# nivel0-2.net
KiCad netlist of a schematic drawn in EAGLE
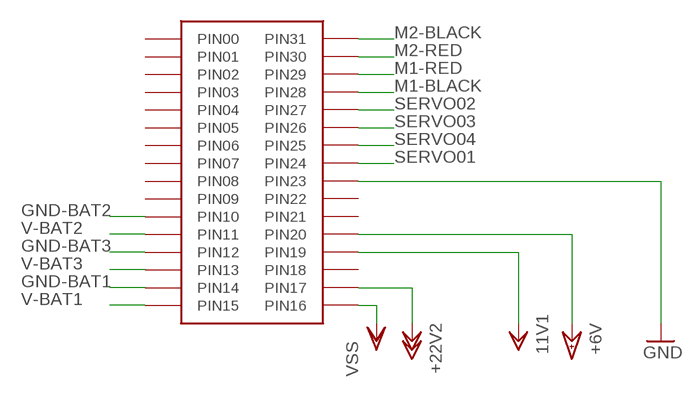
[diagram p0: schematic, sheet 1]
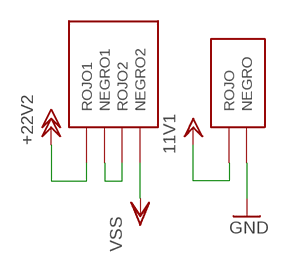
[diagram p1: schematic, sheet 2]
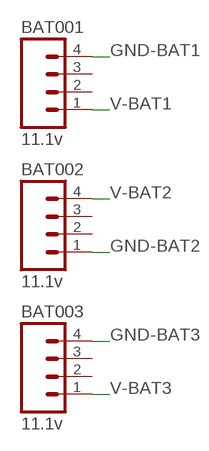
[diagram p2: schematic, sheet 3]
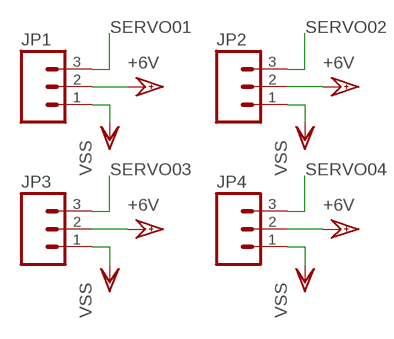
[diagram p3: schematic, sheet 4]
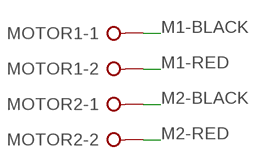
[diagram p4: schematic, sheet 5]

(export (version "E")
  (design (tool "Eeschema 10.0.6"))
  (components
    (comp (ref "U$11")
      (value "CONECTOR_AUDIO")
      (footprint "eagle-import:CONECTOR_AUDIO")
      (libsource (lib "eagle-import") (part "CONECTOR_AUDIO"))
    )
    (comp (ref "U$12")
      (value "CONECTOR_AUDIO2")
      (footprint "eagle-import:CONECTOR_AUDIO2")
      (libsource (lib "eagle-import") (part "CONECTOR_AUDIO2"))
    )
    (comp (ref "BAT001")
      (value "11.1v")
      (footprint "eagle-import:1X04_LONGPADS")
      (libsource (lib "eagle-import") (part "M04LONGPADS"))
    )
    (comp (ref "BAT002")
      (value "11.1v")
      (footprint "eagle-import:1X04_LONGPADS")
      (libsource (lib "eagle-import") (part "M04LONGPADS"))
    )
    (comp (ref "BAT003")
      (value "11.1v")
      (footprint "eagle-import:1X04_LONGPADS")
      (libsource (lib "eagle-import") (part "M04LONGPADS"))
    )
    (comp (ref "MOTOR1")
      (value "W237-02P")
      (footprint "eagle-import:W237-132")
      (libsource (lib "eagle-import") (part "W237-02P"))
    )
    (comp (ref "MOTOR2")
      (value "W237-02P")
      (footprint "eagle-import:W237-132")
      (libsource (lib "eagle-import") (part "W237-02P"))
    )
    (comp (ref "JP1")
      (value "M03LONGPADS")
      (footprint "eagle-import:1X03_LONGPADS")
      (libsource (lib "eagle-import") (part "M03LONGPADS"))
    )
    (comp (ref "JP2")
      (value "M03LONGPADS")
      (footprint "eagle-import:1X03_LONGPADS")
      (libsource (lib "eagle-import") (part "M03LONGPADS"))
    )
    (comp (ref "JP3")
      (value "M03LONGPADS")
      (footprint "eagle-import:1X03_LONGPADS")
      (libsource (lib "eagle-import") (part "M03LONGPADS"))
    )
    (comp (ref "JP4")
      (value "M03LONGPADS")
      (footprint "eagle-import:1X03_LONGPADS")
      (libsource (lib "eagle-import") (part "M03LONGPADS"))
    )
    (comp (ref "U$1")
      (value "BASE")
      (footprint "eagle-import:BASE")
      (libsource (lib "eagle-import") (part "BASE"))
    )
  )
  (nets
    (net (code "1") (name "+6V") (class "Default")
      (node (ref "JP1") (pin "2") (pinfunction "2_2") (pintype "passive"))
      (node (ref "JP2") (pin "2") (pinfunction "2_2") (pintype "passive"))
      (node (ref "JP3") (pin "2") (pinfunction "2_2") (pintype "passive"))
      (node (ref "JP4") (pin "2") (pinfunction "2_2") (pintype "passive"))
      (node (ref "U$1") (pin "PIN20") (pinfunction "PIN20_PIN20") (pintype "bidirectional"))
    )
    (net (code "2") (name "+11V1") (class "Default")
      (node (ref "U$1") (pin "PIN19") (pinfunction "PIN19_PIN19") (pintype "bidirectional"))
      (node (ref "U$12") (pin "P$2") (pinfunction "ROJO_P$2") (pintype "bidirectional"))
    )
    (net (code "3") (name "+22V") (class "Default")
      (node (ref "U$1") (pin "PIN17") (pinfunction "PIN17_PIN17") (pintype "bidirectional"))
      (node (ref "U$11") (pin "P$1") (pinfunction "ROJO1_P$1") (pintype "bidirectional"))
    )
    (net (code "4") (name "GND") (class "Default")
      (node (ref "U$1") (pin "PIN23") (pinfunction "PIN23_PIN23") (pintype "bidirectional"))
      (node (ref "U$12") (pin "P$1") (pinfunction "NEGRO_P$1") (pintype "bidirectional"))
    )
    (net (code "5") (name "GND-BAT1") (class "Default")
      (node (ref "BAT001") (pin "4") (pinfunction "4_4") (pintype "passive"))
      (node (ref "U$1") (pin "PIN14") (pinfunction "PIN14_PIN14") (pintype "bidirectional"))
    )
    (net (code "6") (name "GND-BAT2") (class "Default")
      (node (ref "BAT002") (pin "1") (pinfunction "1_1") (pintype "passive"))
      (node (ref "U$1") (pin "PIN10") (pinfunction "PIN10_PIN10") (pintype "bidirectional"))
    )
    (net (code "7") (name "GND-BAT3") (class "Default")
      (node (ref "BAT003") (pin "4") (pinfunction "4_4") (pintype "passive"))
      (node (ref "U$1") (pin "PIN12") (pinfunction "PIN12_PIN12") (pintype "bidirectional"))
    )
    (net (code "8") (name "M1-BLACK") (class "Default")
      (node (ref "MOTOR1") (pin "1") (pinfunction "KL_1") (pintype "passive"))
      (node (ref "U$1") (pin "PIN28") (pinfunction "PIN28_PIN28") (pintype "bidirectional"))
    )
    (net (code "9") (name "M1-RED") (class "Default")
      (node (ref "MOTOR1") (pin "2") (pinfunction "KL_2") (pintype "passive"))
      (node (ref "U$1") (pin "PIN29") (pinfunction "PIN29_PIN29") (pintype "bidirectional"))
    )
    (net (code "10") (name "M2-BLACK") (class "Default")
      (node (ref "MOTOR2") (pin "1") (pinfunction "KL_1") (pintype "passive"))
      (node (ref "U$1") (pin "PIN31") (pinfunction "PIN31_PIN31") (pintype "bidirectional"))
    )
    (net (code "11") (name "M2-RED") (class "Default")
      (node (ref "MOTOR2") (pin "2") (pinfunction "KL_2") (pintype "passive"))
      (node (ref "U$1") (pin "PIN30") (pinfunction "PIN30_PIN30") (pintype "bidirectional"))
    )
    (net (code "12") (name "Net-(U$11-NEGRO1)") (class "Default")
      (node (ref "U$11") (pin "P$2") (pinfunction "NEGRO1_P$2") (pintype "bidirectional"))
      (node (ref "U$11") (pin "P$3") (pinfunction "ROJO2_P$3") (pintype "bidirectional"))
    )
    (net (code "13") (name "SERVO01") (class "Default")
      (node (ref "JP1") (pin "3") (pinfunction "3_3") (pintype "passive"))
      (node (ref "U$1") (pin "PIN24") (pinfunction "PIN24_PIN24") (pintype "bidirectional"))
    )
    (net (code "14") (name "SERVO02") (class "Default")
      (node (ref "JP2") (pin "3") (pinfunction "3_3") (pintype "passive"))
      (node (ref "U$1") (pin "PIN27") (pinfunction "PIN27_PIN27") (pintype "bidirectional"))
    )
    (net (code "15") (name "SERVO03") (class "Default")
      (node (ref "JP3") (pin "3") (pinfunction "3_3") (pintype "passive"))
      (node (ref "U$1") (pin "PIN26") (pinfunction "PIN26_PIN26") (pintype "bidirectional"))
    )
    (net (code "16") (name "SERVO04") (class "Default")
      (node (ref "JP4") (pin "3") (pinfunction "3_3") (pintype "passive"))
      (node (ref "U$1") (pin "PIN25") (pinfunction "PIN25_PIN25") (pintype "bidirectional"))
    )
    (net (code "17") (name "V-BAT1") (class "Default")
      (node (ref "BAT001") (pin "1") (pinfunction "1_1") (pintype "passive"))
      (node (ref "U$1") (pin "PIN15") (pinfunction "PIN15_PIN15") (pintype "bidirectional"))
    )
    (net (code "18") (name "V-BAT2") (class "Default")
      (node (ref "BAT002") (pin "4") (pinfunction "4_4") (pintype "passive"))
      (node (ref "U$1") (pin "PIN11") (pinfunction "PIN11_PIN11") (pintype "bidirectional"))
    )
    (net (code "19") (name "V-BAT3") (class "Default")
      (node (ref "BAT003") (pin "1") (pinfunction "1_1") (pintype "passive"))
      (node (ref "U$1") (pin "PIN13") (pinfunction "PIN13_PIN13") (pintype "bidirectional"))
    )
    (net (code "20") (name "VSS") (class "Default")
      (node (ref "JP1") (pin "1") (pinfunction "1_1") (pintype "passive"))
      (node (ref "JP2") (pin "1") (pinfunction "1_1") (pintype "passive"))
      (node (ref "JP3") (pin "1") (pinfunction "1_1") (pintype "passive"))
      (node (ref "JP4") (pin "1") (pinfunction "1_1") (pintype "passive"))
      (node (ref "U$1") (pin "PIN16") (pinfunction "PIN16_PIN16") (pintype "bidirectional"))
      (node (ref "U$11") (pin "P$4") (pinfunction "NEGRO2_P$4") (pintype "bidirectional"))
    )
    (net (code "21") (name "unconnected-(BAT001-Pad2)") (class "Default")
      (node (ref "BAT001") (pin "2") (pinfunction "2_2") (pintype "passive"))
    )
    (net (code "22") (name "unconnected-(BAT001-Pad3)") (class "Default")
      (node (ref "BAT001") (pin "3") (pinfunction "3_3") (pintype "passive"))
    )
    (net (code "23") (name "unconnected-(BAT002-Pad2)") (class "Default")
      (node (ref "BAT002") (pin "2") (pinfunction "2_2") (pintype "passive"))
    )
    (net (code "24") (name "unconnected-(BAT002-Pad3)") (class "Default")
      (node (ref "BAT002") (pin "3") (pinfunction "3_3") (pintype "passive"))
    )
    (net (code "25") (name "unconnected-(BAT003-Pad2)") (class "Default")
      (node (ref "BAT003") (pin "2") (pinfunction "2_2") (pintype "passive"))
    )
    (net (code "26") (name "unconnected-(BAT003-Pad3)") (class "Default")
      (node (ref "BAT003") (pin "3") (pinfunction "3_3") (pintype "passive"))
    )
    (net (code "27") (name "unconnected-(U$1-PadPIN00)") (class "Default")
      (node (ref "U$1") (pin "PIN00") (pinfunction "PIN00_PIN00") (pintype "bidirectional"))
    )
    (net (code "28") (name "unconnected-(U$1-PadPIN01)") (class "Default")
      (node (ref "U$1") (pin "PIN01") (pinfunction "PIN01_PIN01") (pintype "bidirectional"))
    )
    (net (code "29") (name "unconnected-(U$1-PadPIN02)") (class "Default")
      (node (ref "U$1") (pin "PIN02") (pinfunction "PIN02_PIN02") (pintype "bidirectional"))
    )
    (net (code "30") (name "unconnected-(U$1-PadPIN03)") (class "Default")
      (node (ref "U$1") (pin "PIN03") (pinfunction "PIN03_PIN03") (pintype "bidirectional"))
    )
    (net (code "31") (name "unconnected-(U$1-PadPIN04)") (class "Default")
      (node (ref "U$1") (pin "PIN04") (pinfunction "PIN04_PIN04") (pintype "bidirectional"))
    )
    (net (code "32") (name "unconnected-(U$1-PadPIN05)") (class "Default")
      (node (ref "U$1") (pin "PIN05") (pinfunction "PIN05_PIN05") (pintype "bidirectional"))
    )
    (net (code "33") (name "unconnected-(U$1-PadPIN06)") (class "Default")
      (node (ref "U$1") (pin "PIN06") (pinfunction "PIN06_PIN06") (pintype "bidirectional"))
    )
    (net (code "34") (name "unconnected-(U$1-PadPIN07)") (class "Default")
      (node (ref "U$1") (pin "PIN07") (pinfunction "PIN07_PIN07") (pintype "bidirectional"))
    )
    (net (code "35") (name "unconnected-(U$1-PadPIN08)") (class "Default")
      (node (ref "U$1") (pin "PIN08") (pinfunction "PIN08_PIN08") (pintype "bidirectional"))
    )
    (net (code "36") (name "unconnected-(U$1-PadPIN09)") (class "Default")
      (node (ref "U$1") (pin "PIN09") (pinfunction "PIN09_PIN09") (pintype "bidirectional"))
    )
    (net (code "37") (name "unconnected-(U$1-PadPIN18)") (class "Default")
      (node (ref "U$1") (pin "PIN18") (pinfunction "PIN18_PIN18") (pintype "bidirectional"))
    )
    (net (code "38") (name "unconnected-(U$1-PadPIN21)") (class "Default")
      (node (ref "U$1") (pin "PIN21") (pinfunction "PIN21_PIN21") (pintype "bidirectional"))
    )
    (net (code "39") (name "unconnected-(U$1-PadPIN22)") (class "Default")
      (node (ref "U$1") (pin "PIN22") (pinfunction "PIN22_PIN22") (pintype "bidirectional"))
    )
  )
)
